# 04_Sensor.net
KiCad netlist of a schematic drawn in Altium Designer
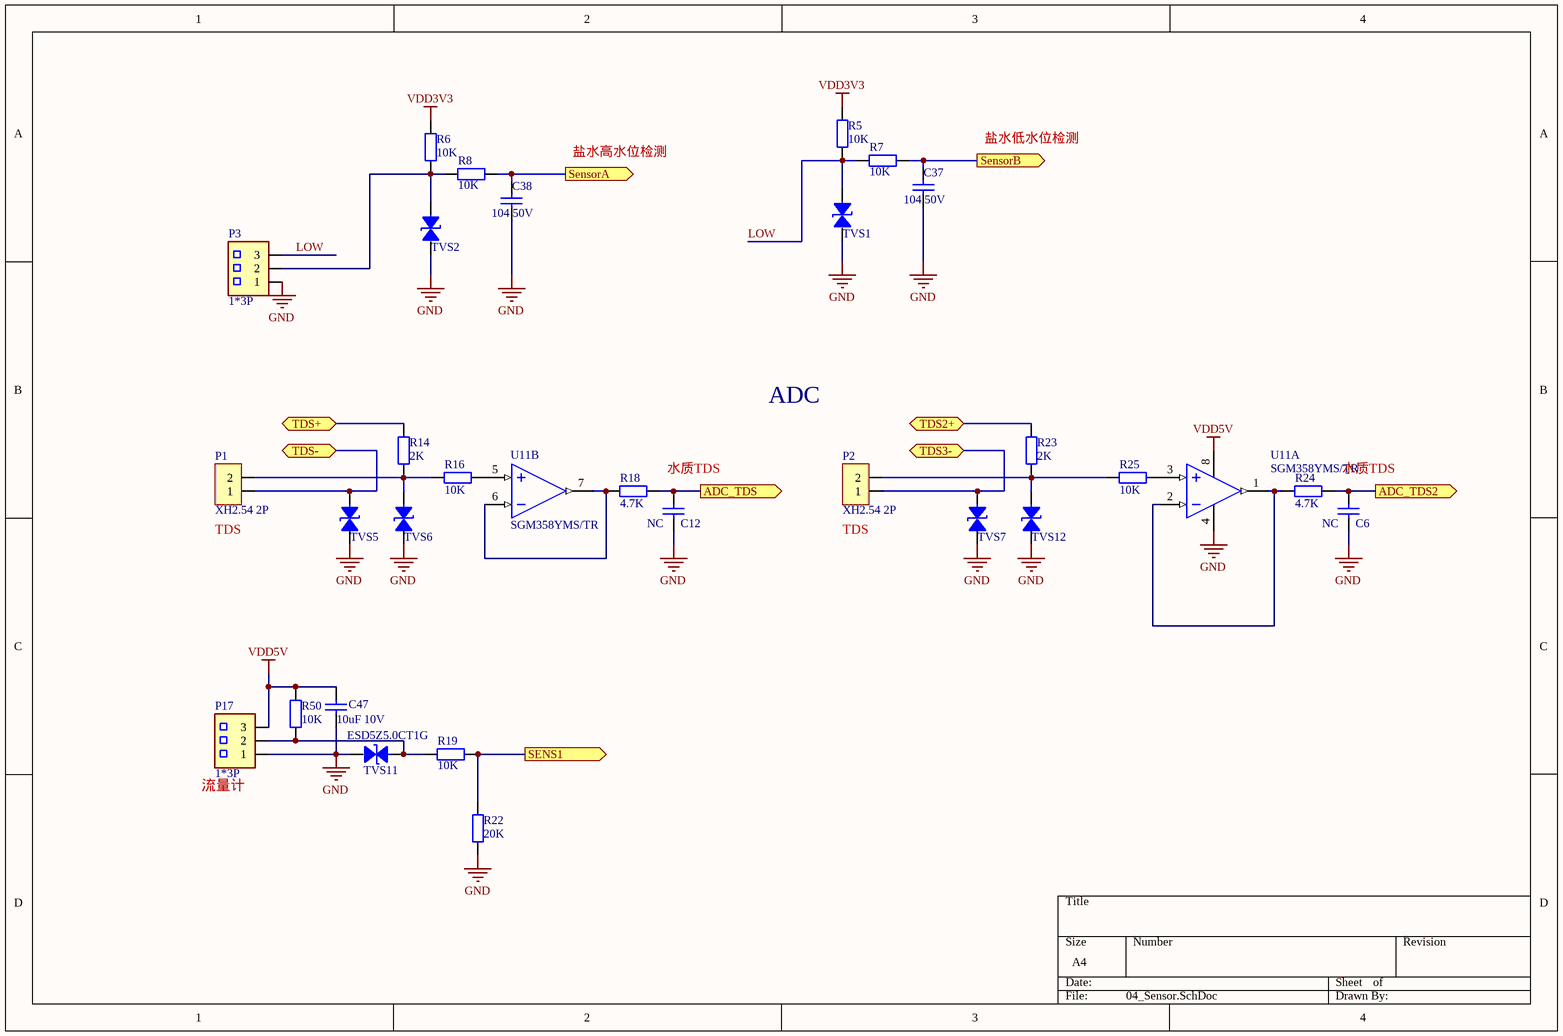
[diagram p0: 04_Sensor.SchDoc]

(export (version "E")
  (design (tool "Eeschema 10.0.6"))
  (components
    (comp (ref "C6")
      (value "NC")
      (footprint "0603C")
      (description "贴片电容 10%")
      (libsource (lib "XiaoyI") (part "CAP4"))
    )
    (comp (ref "C12")
      (value "NC")
      (footprint "SMD-0603C")
      (description "贴片电容 10%")
      (libsource (lib "XiaoyI") (part "CAP4"))
    )
    (comp (ref "C37")
      (value "104 50V")
      (footprint "SMD-0603C")
      (description "贴片电容 20%")
      (libsource (lib "XiaoyI") (part "CAP4"))
    )
    (comp (ref "C38")
      (value "104 50V")
      (footprint "SMD-0603C")
      (description "贴片电容 20%")
      (libsource (lib "XiaoyI") (part "CAP4"))
    )
    (comp (ref "C47")
      (value "10uF 10V")
      (footprint "SMD-0603C")
      (description "贴片电容 10%")
      (libsource (lib "Miscellaneous Devices LC") (part "0805 22uF (226) 20% 25V"))
    )
    (comp (ref "P1")
      (value "XH2.54 2P")
      (footprint "SIP-2A")
      (description "XH2.54 2P 直插")
      (libsource (lib "XiaoyI") (part "SIP-2"))
    )
    (comp (ref "P2")
      (value "XH2.54 2P")
      (footprint "SIP-2A")
      (description "XH2.54 2P 直插")
      (libsource (lib "XiaoyI") (part "SIP-2"))
    )
    (comp (ref "P3") (value "1*3P") (footprint "3X2MMZ") (libsource (lib "PARK-N5 V1.0") (part "HDR1*3")))
    (comp (ref "P17")
      (value "1*3P")
      (footprint "3X2.54MMZ2")
      (libsource (lib "PARK-N5 V1.0") (part "HDR1*3"))
    )
    (comp (ref "R5")
      (value "10K")
      (footprint "SMD-0603")
      (description "贴片电阻 1%")
      (libsource (lib "ABB") (part "RES0"))
    )
    (comp (ref "R6")
      (value "10K")
      (footprint "SMD-0603")
      (description "贴片电阻 1%")
      (libsource (lib "ABB") (part "RES0"))
    )
    (comp (ref "R7")
      (value "10K")
      (footprint "SMD-0603")
      (description "贴片电阻 1%")
      (libsource (lib "") (part "RES0_1"))
    )
    (comp (ref "R8")
      (value "10K")
      (footprint "SMD-0603")
      (description "贴片电阻 1%")
      (libsource (lib "") (part "RES0_1"))
    )
    (comp (ref "R14")
      (value "2K")
      (footprint "SMD-0603")
      (description "贴片电阻 1%")
      (libsource (lib "ABB") (part "RES0"))
    )
    (comp (ref "R16")
      (value "10K")
      (footprint "SMD-0603")
      (description "贴片电阻 1%")
      (libsource (lib "") (part "RES0_1"))
    )
    (comp (ref "R18")
      (value "4.7K")
      (footprint "SMD-0603")
      (description "贴片电阻 5%")
      (libsource (lib "") (part "RES0_2"))
    )
    (comp (ref "R19")
      (value "10K")
      (footprint "SMD-0603")
      (description "贴片电阻 5%")
      (libsource (lib "") (part "0603 10KΩ (1002) 1%_1"))
    )
    (comp (ref "R22")
      (value "20K")
      (footprint "SMD-0603")
      (description "贴片电阻 5%")
      (libsource (lib "") (part "0603 10KΩ (1002) 1%_2"))
    )
    (comp (ref "R23")
      (value "2K")
      (footprint "0603R")
      (description "贴片电阻 1%")
      (libsource (lib "ABB") (part "RES0"))
    )
    (comp (ref "R24")
      (value "4.7K")
      (footprint "0603R")
      (description "贴片电阻 5%")
      (libsource (lib "") (part "RES0_2"))
    )
    (comp (ref "R25")
      (value "10K")
      (footprint "SMD-0603")
      (description "贴片电阻 1%")
      (libsource (lib "") (part "RES0_1"))
    )
    (comp (ref "R50")
      (value "10K")
      (footprint "SMD-0603")
      (description "贴片电阻 5%")
      (libsource (lib "Miscellaneous Devices LC") (part "0603 10KΩ (1002) 1%"))
    )
    (comp (ref "TVS1")
      (value "ESD5Z5.0CT1G")
      (footprint "SOD-523")
      (description "TVS")
      (libsource (lib "XiaoyI") (part "TVS-1"))
    )
    (comp (ref "TVS2")
      (value "ESD5Z5.0CT1G")
      (footprint "SOD-523")
      (description "TVS")
      (libsource (lib "XiaoyI") (part "TVS-1"))
    )
    (comp (ref "TVS5")
      (value "ESD5Z5.0CT1G")
      (footprint "SOD-523")
      (description "TVS")
      (libsource (lib "XiaoyI") (part "TVS-1"))
    )
    (comp (ref "TVS6")
      (value "ESD5Z5.0CT1G")
      (footprint "SOD-523")
      (description "TVS")
      (libsource (lib "XiaoyI") (part "TVS-1"))
    )
    (comp (ref "TVS7")
      (value "ESD5Z5.0CT1G")
      (footprint "SOD-523")
      (description "TVS")
      (libsource (lib "XiaoyI") (part "TVS-1"))
    )
    (comp (ref "TVS11")
      (value "ESD5Z5.0CT1G")
      (footprint "SOD-523")
      (description "TVS 5.0V")
      (libsource (lib "XiaoyI") (part "TVS-1"))
    )
    (comp (ref "TVS12")
      (value "ESD5Z5.0CT1G")
      (footprint "SOD-523")
      (description "TVS")
      (libsource (lib "XiaoyI") (part "TVS-1"))
    )
    (comp (ref "U11")
      (value "SGM358YMS/TR")
      (footprint "MSOP-8")
      (description "运算放大器")
      (libsource (lib "电解水杯V1.1_ZM_20210702") (part "LM358"))
    )
  )
  (nets
    (net (code "1") (name "/ADC_TDS") (class "Default")
      (node (ref "C12") (pin "2") (pinfunction "2_2") (pintype "passive"))
      (node (ref "R18") (pin "1") (pinfunction "1_1") (pintype "passive"))
    )
    (net (code "2") (name "/ADC_TDS2") (class "Default")
      (node (ref "C6") (pin "2") (pinfunction "2_2") (pintype "passive"))
      (node (ref "R24") (pin "1") (pinfunction "1_1") (pintype "passive"))
    )
    (net (code "3") (name "/LOW") (class "Default")
      (node (ref "P3") (pin "3") (pinfunction "3_3") (pintype "passive"))
      (node (ref "R5") (pin "2") (pinfunction "2_2") (pintype "passive"))
      (node (ref "R7") (pin "1") (pinfunction "1_1") (pintype "passive"))
      (node (ref "TVS1") (pin "2") (pinfunction "B_2") (pintype "passive"))
    )
    (net (code "4") (name "/SENS1") (class "Default")
      (node (ref "R19") (pin "2") (pinfunction "2_2") (pintype "passive"))
      (node (ref "R22") (pin "2") (pinfunction "2_2") (pintype "passive"))
    )
    (net (code "5") (name "/SensorA") (class "Default")
      (node (ref "C38") (pin "2") (pinfunction "2_2") (pintype "passive"))
      (node (ref "R8") (pin "2") (pinfunction "2_2") (pintype "passive"))
    )
    (net (code "6") (name "/SensorB") (class "Default")
      (node (ref "C37") (pin "2") (pinfunction "2_2") (pintype "passive"))
      (node (ref "R7") (pin "2") (pinfunction "2_2") (pintype "passive"))
    )
    (net (code "7") (name "/TDS+") (class "Default")
      (node (ref "R14") (pin "1") (pinfunction "1_1") (pintype "passive"))
    )
    (net (code "8") (name "/TDS-") (class "Default")
      (node (ref "P1") (pin "1") (pinfunction "1_1") (pintype "passive"))
      (node (ref "TVS5") (pin "2") (pinfunction "B_2") (pintype "passive"))
    )
    (net (code "9") (name "/TDS2+") (class "Default")
      (node (ref "R23") (pin "1") (pinfunction "1_1") (pintype "passive"))
    )
    (net (code "10") (name "/TDS3-") (class "Default")
      (node (ref "P2") (pin "1") (pinfunction "1_1") (pintype "passive"))
      (node (ref "TVS7") (pin "2") (pinfunction "B_2") (pintype "passive"))
    )
    (net (code "11") (name "GND") (class "Default")
      (node (ref "C12") (pin "1") (pinfunction "1_1") (pintype "passive"))
      (node (ref "C37") (pin "1") (pinfunction "1_1") (pintype "passive"))
      (node (ref "C38") (pin "1") (pinfunction "1_1") (pintype "passive"))
      (node (ref "C47") (pin "1") (pinfunction "1_1") (pintype "passive"))
      (node (ref "C6") (pin "1") (pinfunction "1_1") (pintype "passive"))
      (node (ref "P17") (pin "1") (pinfunction "1_1") (pintype "passive"))
      (node (ref "P3") (pin "1") (pinfunction "1_1") (pintype "passive"))
      (node (ref "R22") (pin "1") (pinfunction "1_1") (pintype "passive"))
      (node (ref "TVS1") (pin "1") (pinfunction "A_1") (pintype "passive"))
      (node (ref "TVS11") (pin "1") (pinfunction "A_1") (pintype "passive"))
      (node (ref "TVS12") (pin "1") (pinfunction "A_1") (pintype "passive"))
      (node (ref "TVS2") (pin "1") (pinfunction "A_1") (pintype "passive"))
      (node (ref "TVS5") (pin "1") (pinfunction "A_1") (pintype "passive"))
      (node (ref "TVS6") (pin "1") (pinfunction "A_1") (pintype "passive"))
      (node (ref "TVS7") (pin "1") (pinfunction "A_1") (pintype "passive"))
      (node (ref "U11") (pin "4") (pinfunction "V-_4") (pintype "power_in"))
    )
    (net (code "12") (name "Net-(TVS2-B)") (class "Default")
      (node (ref "P3") (pin "2") (pinfunction "2_2") (pintype "passive"))
      (node (ref "R6") (pin "2") (pinfunction "2_2") (pintype "passive"))
      (node (ref "R8") (pin "1") (pinfunction "1_1") (pintype "passive"))
      (node (ref "TVS2") (pin "2") (pinfunction "B_2") (pintype "passive"))
    )
    (net (code "13") (name "Net-(TVS6-B)") (class "Default")
      (node (ref "P1") (pin "2") (pinfunction "2_2") (pintype "passive"))
      (node (ref "R14") (pin "2") (pinfunction "2_2") (pintype "passive"))
      (node (ref "R16") (pin "1") (pinfunction "1_1") (pintype "passive"))
      (node (ref "TVS6") (pin "2") (pinfunction "B_2") (pintype "passive"))
    )
    (net (code "14") (name "Net-(TVS11-B)") (class "Default")
      (node (ref "P17") (pin "2") (pinfunction "2_2") (pintype "passive"))
      (node (ref "R19") (pin "1") (pinfunction "1_1") (pintype "passive"))
      (node (ref "R50") (pin "2") (pinfunction "2_2") (pintype "passive"))
      (node (ref "TVS11") (pin "2") (pinfunction "B_2") (pintype "passive"))
    )
    (net (code "15") (name "Net-(TVS12-B)") (class "Default")
      (node (ref "P2") (pin "2") (pinfunction "2_2") (pintype "passive"))
      (node (ref "R23") (pin "2") (pinfunction "2_2") (pintype "passive"))
      (node (ref "R25") (pin "1") (pinfunction "1_1") (pintype "passive"))
      (node (ref "TVS12") (pin "2") (pinfunction "B_2") (pintype "passive"))
    )
    (net (code "16") (name "Net-(U11A-IN1+)") (class "Default")
      (node (ref "R25") (pin "2") (pinfunction "2_2") (pintype "passive"))
      (node (ref "U11") (pin "3") (pinfunction "IN1+_3") (pintype "input"))
    )
    (net (code "17") (name "Net-(U11A-IN1-)") (class "Default")
      (node (ref "R24") (pin "2") (pinfunction "2_2") (pintype "passive"))
      (node (ref "U11") (pin "1") (pinfunction "OUT1_1") (pintype "output"))
      (node (ref "U11") (pin "2") (pinfunction "IN1-_2") (pintype "input"))
    )
    (net (code "18") (name "Net-(U11B-IN2+)") (class "Default")
      (node (ref "R16") (pin "2") (pinfunction "2_2") (pintype "passive"))
      (node (ref "U11") (pin "5") (pinfunction "IN2+_5") (pintype "input"))
    )
    (net (code "19") (name "Net-(U11B-IN2-)") (class "Default")
      (node (ref "R18") (pin "2") (pinfunction "2_2") (pintype "passive"))
      (node (ref "U11") (pin "6") (pinfunction "IN2-_6") (pintype "input"))
      (node (ref "U11") (pin "7") (pinfunction "OUT2_7") (pintype "output"))
    )
    (net (code "20") (name "VDD3V3") (class "Default")
      (node (ref "R5") (pin "1") (pinfunction "1_1") (pintype "passive"))
      (node (ref "R6") (pin "1") (pinfunction "1_1") (pintype "passive"))
    )
    (net (code "21") (name "VDD5V") (class "Default")
      (node (ref "C47") (pin "2") (pinfunction "2_2") (pintype "passive"))
      (node (ref "P17") (pin "3") (pinfunction "3_3") (pintype "passive"))
      (node (ref "R50") (pin "1") (pinfunction "1_1") (pintype "passive"))
      (node (ref "U11") (pin "8") (pinfunction "V+_8") (pintype "power_in"))
    )
  )
)
